# new_9DOF.net
KiCad netlist of a schematic drawn in EAGLE
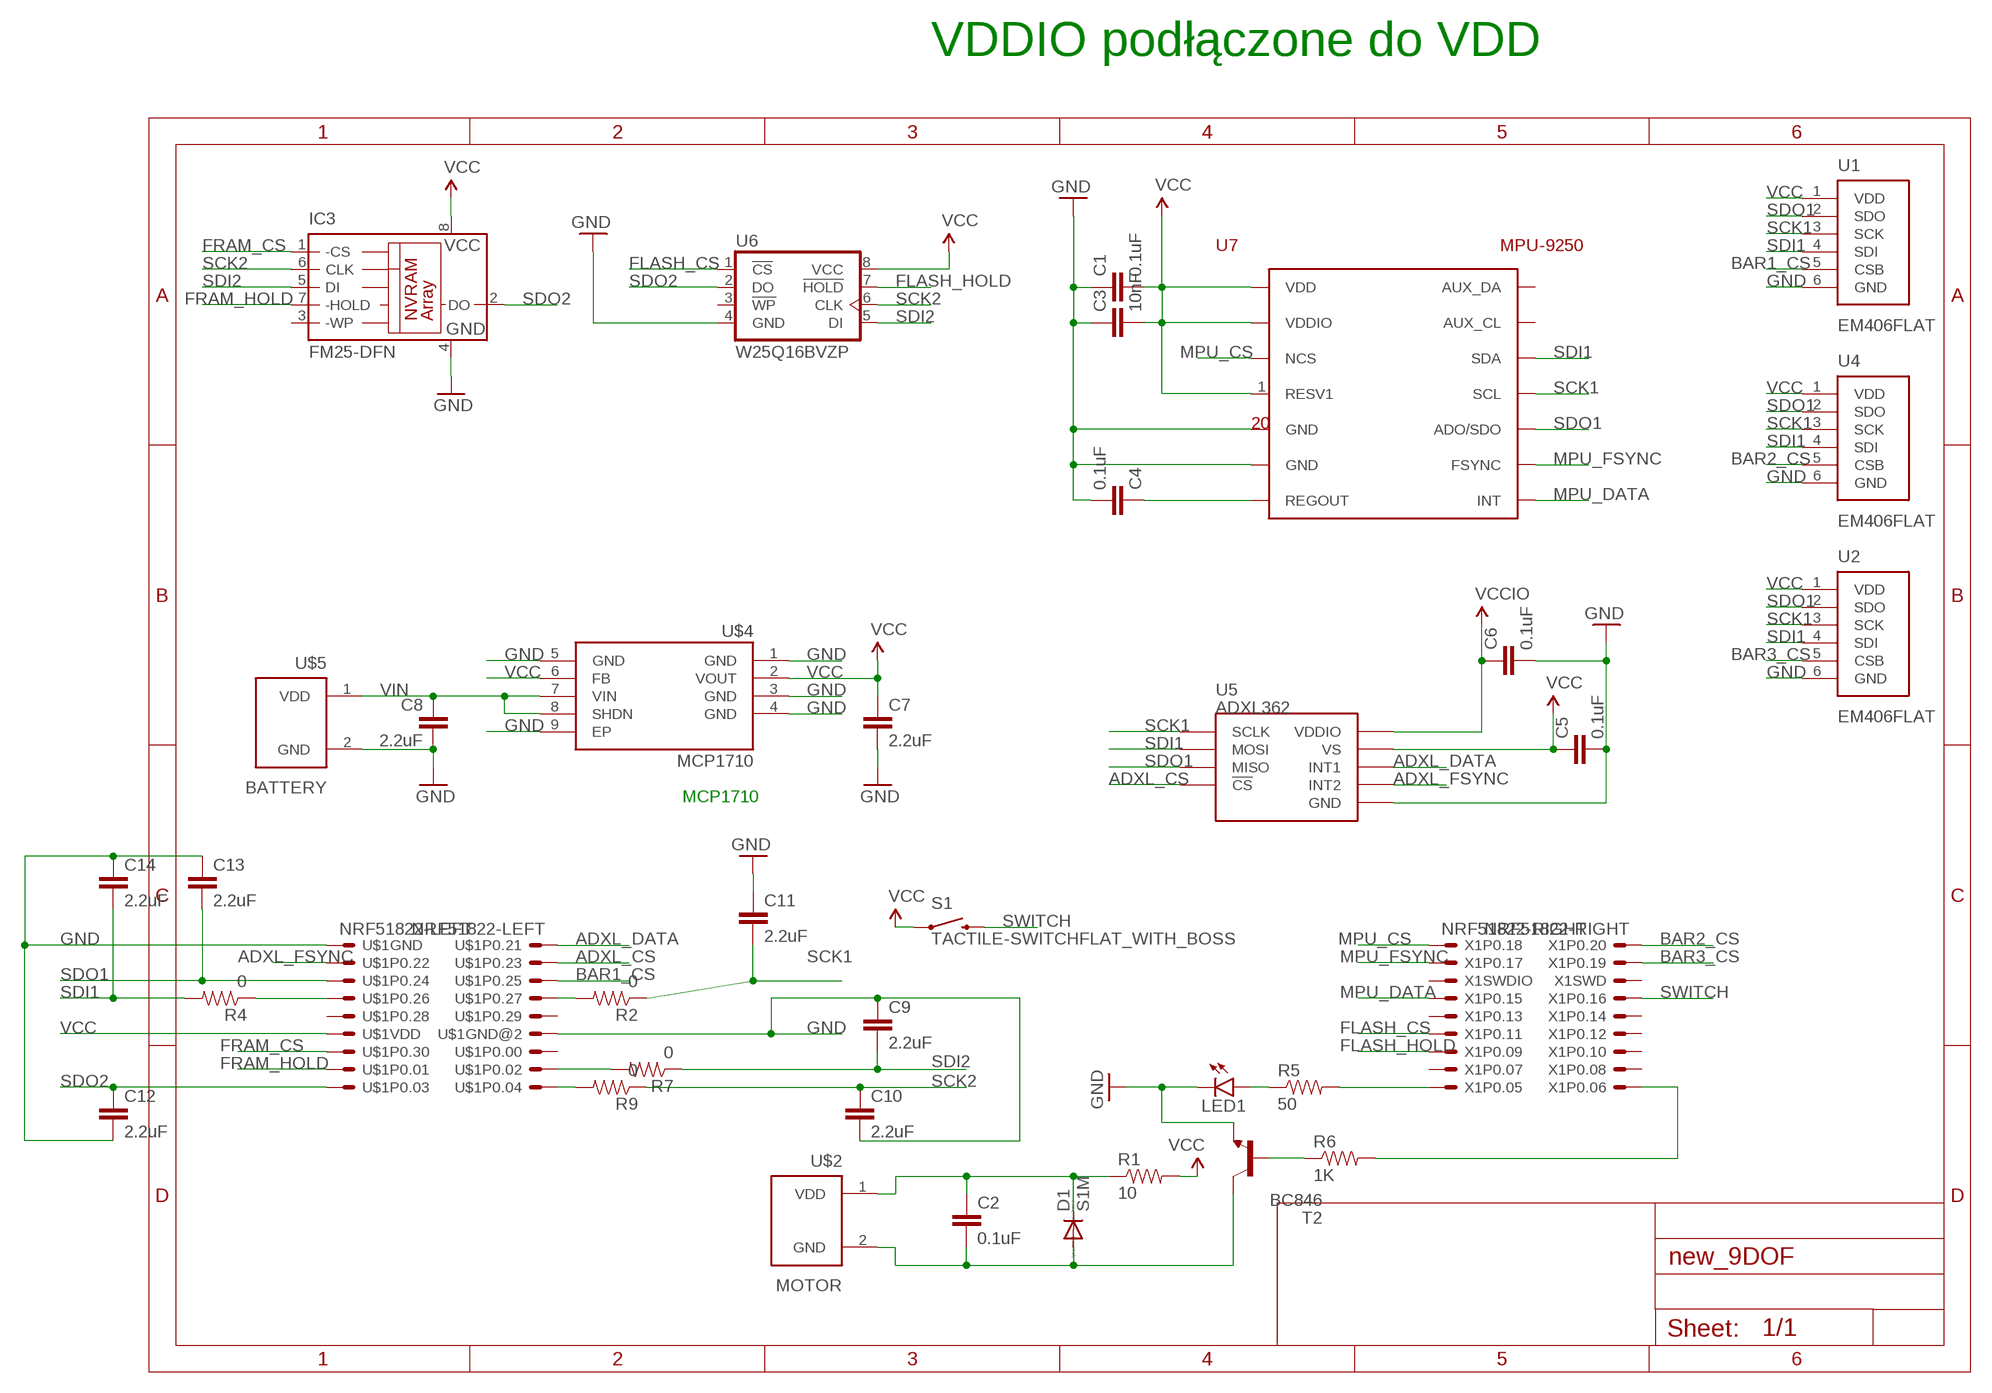
[diagram p0: schematic, sheet 1]

(export (version "E")
  (design (tool "Eeschema 10.0.6"))
  (components
    (comp (ref "C1")
      (value "0.1uF")
      (footprint "eagle-import:0603-CAP")
      (libsource (lib "eagle-import") (part "0.1UF-25V(+80/-20%)(0603)"))
    )
    (comp (ref "C2")
      (value "0.1uF")
      (footprint "eagle-import:0603-CAP")
      (libsource (lib "eagle-import") (part "0.1UF-25V(+80/-20%)(0603)"))
    )
    (comp (ref "C3")
      (value "10nF")
      (footprint "eagle-import:0603-CAP")
      (libsource (lib "eagle-import") (part "0.1UF-25V(+80/-20%)(0603)"))
    )
    (comp (ref "C4")
      (value "0.1uF")
      (footprint "eagle-import:0603-CAP")
      (libsource (lib "eagle-import") (part "0.1UF-25V(+80/-20%)(0603)"))
    )
    (comp (ref "C5")
      (value "0.1uF")
      (footprint "eagle-import:0603-CAP")
      (libsource (lib "eagle-import") (part "0.1UF-25V(+80/-20%)(0603)"))
    )
    (comp (ref "C6")
      (value "0.1uF")
      (footprint "eagle-import:0603-CAP")
      (libsource (lib "eagle-import") (part "0.1UF-25V(+80/-20%)(0603)"))
    )
    (comp (ref "C7")
      (value "2.2uF")
      (footprint "eagle-import:0603-CAP")
      (libsource (lib "eagle-import") (part "0.1UF-25V(+80/-20%)(0603)"))
    )
    (comp (ref "C8")
      (value "2.2uF")
      (footprint "eagle-import:0603-CAP")
      (libsource (lib "eagle-import") (part "0.1UF-25V(+80/-20%)(0603)"))
    )
    (comp (ref "C9")
      (value "2.2uF")
      (footprint "eagle-import:0603-CAP")
      (libsource (lib "eagle-import") (part "0.1UF-25V(+80/-20%)(0603)"))
    )
    (comp (ref "C10")
      (value "2.2uF")
      (footprint "eagle-import:0603-CAP")
      (libsource (lib "eagle-import") (part "0.1UF-25V(+80/-20%)(0603)"))
    )
    (comp (ref "C11")
      (value "2.2uF")
      (footprint "eagle-import:0603-CAP")
      (libsource (lib "eagle-import") (part "0.1UF-25V(+80/-20%)(0603)"))
    )
    (comp (ref "C12")
      (value "2.2uF")
      (footprint "eagle-import:0603-CAP")
      (libsource (lib "eagle-import") (part "0.1UF-25V(+80/-20%)(0603)"))
    )
    (comp (ref "C13")
      (value "2.2uF")
      (footprint "eagle-import:0603-CAP")
      (libsource (lib "eagle-import") (part "0.1UF-25V(+80/-20%)(0603)"))
    )
    (comp (ref "C14")
      (value "2.2uF")
      (footprint "eagle-import:0603-CAP")
      (libsource (lib "eagle-import") (part "0.1UF-25V(+80/-20%)(0603)"))
    )
    (comp (ref "D1")
      (value "S1M")
      (footprint "eagle-import:SMA")
      (libsource (lib "eagle-import") (part "S1M"))
    )
    (comp (ref "IC3")
      (value "FM25-DFN")
      (footprint "eagle-import:DFN-8")
      (libsource (lib "eagle-import") (part "FM25-DFN"))
    )
    (comp (ref "LED1")
      (value "LED0603")
      (footprint "eagle-import:LED-0603")
      (libsource (lib "eagle-import") (part "LED0603"))
    )
    (comp (ref "R1")
      (value "10")
      (footprint "eagle-import:0603-RES")
      (libsource (lib "eagle-import") (part "1KOHM1/10W1%(0603)"))
    )
    (comp (ref "R2")
      (value "0")
      (footprint "eagle-import:0603-RES")
      (libsource (lib "eagle-import") (part "100OHM1/10W1%(0603)"))
    )
    (comp (ref "R4")
      (value "0")
      (footprint "eagle-import:0603-RES")
      (libsource (lib "eagle-import") (part "100OHM1/10W1%(0603)"))
    )
    (comp (ref "R5")
      (value "50")
      (footprint "eagle-import:0603-RES")
      (libsource (lib "eagle-import") (part "100OHM1/10W1%(0603)"))
    )
    (comp (ref "R6")
      (value "1K")
      (footprint "eagle-import:0603-RES")
      (libsource (lib "eagle-import") (part "1KOHM1/10W1%(0603)"))
    )
    (comp (ref "R7")
      (value "0")
      (footprint "eagle-import:0603-RES")
      (libsource (lib "eagle-import") (part "100OHM1/10W1%(0603)"))
    )
    (comp (ref "R9")
      (value "0")
      (footprint "eagle-import:0603-RES")
      (libsource (lib "eagle-import") (part "100OHM1/10W1%(0603)"))
    )
    (comp (ref "S1")
      (value "TACTILE-SWITCHFLAT_WITH_BOSS")
      (footprint "eagle-import:TACTILE-SWITCH-SMD")
      (libsource (lib "eagle-import") (part "TACTILE-SWITCHFLAT_WITH_BOSS"))
    )
    (comp (ref "T2")
      (value "BC846")
      (footprint "eagle-import:SOT23")
      (libsource (lib "eagle-import") (part "BC846"))
    )
    (comp (ref "U$1")
      (value "NRF51822-LEFT")
      (footprint "eagle-import:NRF51822-LEFT")
      (fields (field (name "MPN") "NRF51822-left"))
      (libsource (lib "eagle-import") (part "NRF51822-LEFT"))
    )
    (comp (ref "U$2")
      (value "MOTOR")
      (footprint "eagle-import:EM406-2PIN")
      (libsource (lib "eagle-import") (part "EM406-2PINFLAT"))
    )
    (comp (ref "U$4")
      (value "MCP1710")
      (footprint "eagle-import:MCP1710")
      (libsource (lib "eagle-import") (part "MCP1710"))
    )
    (comp (ref "U$5")
      (value "BATTERY")
      (footprint "eagle-import:EM406-2PIN")
      (libsource (lib "eagle-import") (part "EM406-2PINFLAT"))
    )
    (comp (ref "U1")
      (value "EM406FLAT")
      (footprint "eagle-import:EM406-FLAT")
      (libsource (lib "eagle-import") (part "EM406FLAT"))
    )
    (comp (ref "U2")
      (value "EM406FLAT")
      (footprint "eagle-import:EM406-FLAT")
      (libsource (lib "eagle-import") (part "EM406FLAT"))
    )
    (comp (ref "U4")
      (value "EM406FLAT")
      (footprint "eagle-import:EM406-FLAT")
      (libsource (lib "eagle-import") (part "EM406FLAT"))
    )
    (comp (ref "U5")
      (value "ADXL362")
      (footprint "eagle-import:ADXL362-1_1")
      (libsource (lib "eagle-import") (part "ADXL362ADXL362-1{colon}1"))
    )
    (comp (ref "U6")
      (value "W25Q16BVZP")
      (footprint "eagle-import:WSON8")
      (libsource (lib "eagle-import") (part "W25Q16BVZP"))
    )
    (comp (ref "U7")
      (value "MPU-9250")
      (footprint "eagle-import:MPU-9250")
      (libsource (lib "eagle-import") (part "MPU-9250"))
    )
    (comp (ref "X1")
      (value "NRF51822-RIGHT")
      (footprint "eagle-import:NRF51822-RIGHT")
      (fields (field (name "MPN") "NRF51822-right"))
      (libsource (lib "eagle-import") (part "NRF51822-RIGHT"))
    )
  )
  (nets
    (net (code "1") (name "/ADXL_CS") (class "Default")
      (node (ref "U$1") (pin "4") (pinfunction "S_4") (pintype "passive"))
      (node (ref "U5") (pin "P$8") (pinfunction "~{CS}_P$8") (pintype "bidirectional"))
    )
    (net (code "2") (name "/ADXL_DATA") (class "Default")
      (node (ref "U$1") (pin "2") (pinfunction "S_2") (pintype "passive"))
      (node (ref "U5") (pin "P$11") (pinfunction "INT1_P$11") (pintype "bidirectional"))
    )
    (net (code "3") (name "/ADXL_FSYNC") (class "Default")
      (node (ref "U$1") (pin "3") (pinfunction "S_3") (pintype "passive"))
      (node (ref "U5") (pin "P$9") (pinfunction "INT2_P$9") (pintype "bidirectional"))
    )
    (net (code "4") (name "/BAR1_CS") (class "Default")
      (node (ref "U$1") (pin "6") (pinfunction "S_6") (pintype "passive"))
      (node (ref "U1") (pin "5") (pinfunction "CSB_5") (pintype "bidirectional"))
    )
    (net (code "5") (name "/BAR2_CS") (class "Default")
      (node (ref "U4") (pin "5") (pinfunction "CSB_5") (pintype "bidirectional"))
      (node (ref "X1") (pin "2") (pinfunction "S_2") (pintype "passive"))
    )
    (net (code "6") (name "/BAR3_CS") (class "Default")
      (node (ref "U2") (pin "5") (pinfunction "CSB_5") (pintype "bidirectional"))
      (node (ref "X1") (pin "4") (pinfunction "S_4") (pintype "passive"))
    )
    (net (code "7") (name "/FLASH_CS") (class "Default")
      (node (ref "U6") (pin "1") (pinfunction "~{CS}_1") (pintype "input"))
      (node (ref "X1") (pin "11") (pinfunction "S_11") (pintype "passive"))
    )
    (net (code "8") (name "/FLASH_HOLD") (class "Default")
      (node (ref "U6") (pin "7") (pinfunction "~{HOLD}_7") (pintype "input"))
      (node (ref "X1") (pin "13") (pinfunction "S_13") (pintype "passive"))
    )
    (net (code "9") (name "/FRAM_CS") (class "Default")
      (node (ref "IC3") (pin "1") (pinfunction "-CS_1") (pintype "input"))
      (node (ref "U$1") (pin "13") (pinfunction "S_13") (pintype "passive"))
    )
    (net (code "10") (name "/FRAM_HOLD") (class "Default")
      (node (ref "IC3") (pin "7") (pinfunction "-HOLD_7") (pintype "input"))
      (node (ref "U$1") (pin "15") (pinfunction "S_15") (pintype "passive"))
    )
    (net (code "11") (name "/MPU_CS") (class "Default")
      (node (ref "U7") (pin "22") (pinfunction "NCS_22") (pintype "bidirectional"))
      (node (ref "X1") (pin "1") (pinfunction "S_1") (pintype "passive"))
    )
    (net (code "12") (name "/MPU_DATA") (class "Default")
      (node (ref "U7") (pin "12") (pinfunction "INT_12") (pintype "bidirectional"))
      (node (ref "X1") (pin "7") (pinfunction "S_7") (pintype "passive"))
    )
    (net (code "13") (name "/MPU_FSYNC") (class "Default")
      (node (ref "U7") (pin "11") (pinfunction "FSYNC_11") (pintype "bidirectional"))
      (node (ref "X1") (pin "3") (pinfunction "S_3") (pintype "passive"))
    )
    (net (code "14") (name "/SCK1") (class "Default")
      (node (ref "C11") (pin "2") (pinfunction "2_2") (pintype "passive"))
      (node (ref "R2") (pin "1") (pinfunction "1_1") (pintype "passive"))
      (node (ref "U1") (pin "3") (pinfunction "SCK_3") (pintype "bidirectional"))
      (node (ref "U2") (pin "3") (pinfunction "SCK_3") (pintype "bidirectional"))
      (node (ref "U4") (pin "3") (pinfunction "SCK_3") (pintype "bidirectional"))
      (node (ref "U5") (pin "P$4") (pinfunction "SCLK_P$4") (pintype "bidirectional"))
      (node (ref "U7") (pin "23") (pinfunction "SCL_23") (pintype "bidirectional"))
    )
    (net (code "15") (name "/SCK2") (class "Default")
      (node (ref "C10") (pin "1") (pinfunction "1_1") (pintype "passive"))
      (node (ref "IC3") (pin "6") (pinfunction "CLK_6") (pintype "input"))
      (node (ref "R9") (pin "1") (pinfunction "1_1") (pintype "passive"))
      (node (ref "U6") (pin "6") (pinfunction "CLK_6") (pintype "input"))
    )
    (net (code "16") (name "/SDI1") (class "Default")
      (node (ref "C14") (pin "2") (pinfunction "2_2") (pintype "passive"))
      (node (ref "R4") (pin "2") (pinfunction "2_2") (pintype "passive"))
      (node (ref "U1") (pin "4") (pinfunction "SDI_4") (pintype "bidirectional"))
      (node (ref "U2") (pin "4") (pinfunction "SDI_4") (pintype "bidirectional"))
      (node (ref "U4") (pin "4") (pinfunction "SDI_4") (pintype "bidirectional"))
      (node (ref "U5") (pin "P$6") (pinfunction "MOSI_P$6") (pintype "bidirectional"))
      (node (ref "U7") (pin "24") (pinfunction "SDA_24") (pintype "bidirectional"))
    )
    (net (code "17") (name "/SDI2") (class "Default")
      (node (ref "C9") (pin "2") (pinfunction "2_2") (pintype "passive"))
      (node (ref "IC3") (pin "5") (pinfunction "DI_5") (pintype "input"))
      (node (ref "R7") (pin "1") (pinfunction "1_1") (pintype "passive"))
      (node (ref "U6") (pin "5") (pinfunction "DI_5") (pintype "input"))
    )
    (net (code "18") (name "/SDO1") (class "Default")
      (node (ref "C13") (pin "2") (pinfunction "2_2") (pintype "passive"))
      (node (ref "U$1") (pin "5") (pinfunction "S_5") (pintype "passive"))
      (node (ref "U1") (pin "2") (pinfunction "SDO_2") (pintype "bidirectional"))
      (node (ref "U2") (pin "2") (pinfunction "SDO_2") (pintype "bidirectional"))
      (node (ref "U4") (pin "2") (pinfunction "SDO_2") (pintype "bidirectional"))
      (node (ref "U5") (pin "P$7") (pinfunction "MISO_P$7") (pintype "bidirectional"))
      (node (ref "U7") (pin "9") (pinfunction "ADO/SDO_9") (pintype "bidirectional"))
    )
    (net (code "19") (name "/SDO2") (class "Default")
      (node (ref "C12") (pin "1") (pinfunction "1_1") (pintype "passive"))
      (node (ref "IC3") (pin "2") (pinfunction "DO_2") (pintype "output"))
      (node (ref "U$1") (pin "17") (pinfunction "S_17") (pintype "passive"))
      (node (ref "U6") (pin "2") (pinfunction "DO_2") (pintype "output"))
    )
    (net (code "20") (name "/SWITCH") (class "Default")
      (node (ref "S1") (pin "2") (pinfunction "2_2") (pintype "passive"))
      (node (ref "X1") (pin "8") (pinfunction "S_8") (pintype "passive"))
    )
    (net (code "21") (name "/VIN") (class "Default")
      (node (ref "C8") (pin "1") (pinfunction "1_1") (pintype "passive"))
      (node (ref "U$4") (pin "7") (pinfunction "VIN_7") (pintype "bidirectional"))
      (node (ref "U$4") (pin "8") (pinfunction "SHDN_8") (pintype "bidirectional"))
      (node (ref "U$5") (pin "1") (pinfunction "VDD_1") (pintype "bidirectional"))
    )
    (net (code "22") (name "GND") (class "Default")
      (node (ref "C1") (pin "1") (pinfunction "1_1") (pintype "passive"))
      (node (ref "C10") (pin "2") (pinfunction "2_2") (pintype "passive"))
      (node (ref "C11") (pin "1") (pinfunction "1_1") (pintype "passive"))
      (node (ref "C12") (pin "2") (pinfunction "2_2") (pintype "passive"))
      (node (ref "C13") (pin "1") (pinfunction "1_1") (pintype "passive"))
      (node (ref "C14") (pin "1") (pinfunction "1_1") (pintype "passive"))
      (node (ref "C3") (pin "1") (pinfunction "1_1") (pintype "passive"))
      (node (ref "C4") (pin "2") (pinfunction "2_2") (pintype "passive"))
      (node (ref "C5") (pin "2") (pinfunction "2_2") (pintype "passive"))
      (node (ref "C6") (pin "2") (pinfunction "2_2") (pintype "passive"))
      (node (ref "C7") (pin "2") (pinfunction "2_2") (pintype "passive"))
      (node (ref "C8") (pin "2") (pinfunction "2_2") (pintype "passive"))
      (node (ref "C9") (pin "1") (pinfunction "1_1") (pintype "passive"))
      (node (ref "IC3") (pin "4") (pinfunction "GND_4") (pintype "power_in"))
      (node (ref "LED1") (pin "C") (pinfunction "C_C") (pintype "passive"))
      (node (ref "T2") (pin "2") (pinfunction "E_2") (pintype "passive"))
      (node (ref "U$1") (pin "1") (pinfunction "S_1") (pintype "passive"))
      (node (ref "U$1") (pin "12") (pinfunction "S_12") (pintype "passive"))
      (node (ref "U$4") (pin "1") (pinfunction "GND_1") (pintype "bidirectional"))
      (node (ref "U$4") (pin "3") (pinfunction "GND_3") (pintype "bidirectional"))
      (node (ref "U$4") (pin "4") (pinfunction "GND_4") (pintype "bidirectional"))
      (node (ref "U$4") (pin "5") (pinfunction "GND_5") (pintype "bidirectional"))
      (node (ref "U$4") (pin "9") (pinfunction "EP_9") (pintype "bidirectional"))
      (node (ref "U$5") (pin "2") (pinfunction "GND_2") (pintype "bidirectional"))
      (node (ref "U1") (pin "6") (pinfunction "GND_6") (pintype "bidirectional"))
      (node (ref "U2") (pin "6") (pinfunction "GND_6") (pintype "bidirectional"))
      (node (ref "U4") (pin "6") (pinfunction "GND_6") (pintype "bidirectional"))
      (node (ref "U5") (pin "P$12") (pinfunction "GND_P$12") (pintype "bidirectional"))
      (node (ref "U5") (pin "P$13") (pinfunction "GND_P$13") (pintype "bidirectional"))
      (node (ref "U5") (pin "P$16") (pinfunction "GND_P$16") (pintype "bidirectional"))
      (node (ref "U6") (pin "4") (pinfunction "GND_4") (pintype "power_in"))
      (node (ref "U7") (pin "18") (pinfunction "GND_18") (pintype "power_in"))
      (node (ref "U7") (pin "20") (pinfunction "GND_20") (pintype "power_in"))
    )
    (net (code "23") (name "Net-(LED1-PadA)") (class "Default")
      (node (ref "LED1") (pin "A") (pinfunction "A_A") (pintype "passive"))
      (node (ref "R5") (pin "1") (pinfunction "1_1") (pintype "passive"))
    )
    (net (code "24") (name "Net-(T2-B)") (class "Default")
      (node (ref "R6") (pin "1") (pinfunction "1_1") (pintype "passive"))
      (node (ref "T2") (pin "1") (pinfunction "B_1") (pintype "passive"))
    )
    (net (code "25") (name "Net-(T2-C)") (class "Default")
      (node (ref "C2") (pin "2") (pinfunction "2_2") (pintype "passive"))
      (node (ref "D1") (pin "A") (pinfunction "A_A") (pintype "passive"))
      (node (ref "T2") (pin "3") (pinfunction "C_3") (pintype "passive"))
      (node (ref "U$2") (pin "2") (pinfunction "GND_2") (pintype "bidirectional"))
    )
    (net (code "26") (name "Net-(U$1E-S)") (class "Default")
      (node (ref "R7") (pin "2") (pinfunction "2_2") (pintype "passive"))
      (node (ref "U$1") (pin "16") (pinfunction "S_16") (pintype "passive"))
    )
    (net (code "27") (name "Net-(U$1G-S)") (class "Default")
      (node (ref "R9") (pin "2") (pinfunction "2_2") (pintype "passive"))
      (node (ref "U$1") (pin "18") (pinfunction "S_18") (pintype "passive"))
    )
    (net (code "28") (name "Net-(U$1M-S)") (class "Default")
      (node (ref "R4") (pin "1") (pinfunction "1_1") (pintype "passive"))
      (node (ref "U$1") (pin "7") (pinfunction "S_7") (pintype "passive"))
    )
    (net (code "29") (name "Net-(U$1N-S)") (class "Default")
      (node (ref "R2") (pin "2") (pinfunction "2_2") (pintype "passive"))
      (node (ref "U$1") (pin "8") (pinfunction "S_8") (pintype "passive"))
    )
    (net (code "30") (name "Net-(U$2-VDD)") (class "Default")
      (node (ref "C2") (pin "1") (pinfunction "1_1") (pintype "passive"))
      (node (ref "D1") (pin "C") (pinfunction "C_C") (pintype "passive"))
      (node (ref "R1") (pin "1") (pinfunction "1_1") (pintype "passive"))
      (node (ref "U$2") (pin "1") (pinfunction "VDD_1") (pintype "bidirectional"))
    )
    (net (code "31") (name "Net-(U7-REGOUT)") (class "Default")
      (node (ref "C4") (pin "1") (pinfunction "1_1") (pintype "passive"))
      (node (ref "U7") (pin "10") (pinfunction "REGOUT_10") (pintype "bidirectional"))
    )
    (net (code "32") (name "Net-(X1A-S)") (class "Default")
      (node (ref "R5") (pin "2") (pinfunction "2_2") (pintype "passive"))
      (node (ref "X1") (pin "17") (pinfunction "S_17") (pintype "passive"))
    )
    (net (code "33") (name "Net-(X1B-S)") (class "Default")
      (node (ref "R6") (pin "2") (pinfunction "2_2") (pintype "passive"))
      (node (ref "X1") (pin "18") (pinfunction "S_18") (pintype "passive"))
    )
    (net (code "34") (name "VCC") (class "Default")
      (node (ref "C1") (pin "2") (pinfunction "2_2") (pintype "passive"))
      (node (ref "C3") (pin "2") (pinfunction "2_2") (pintype "passive"))
      (node (ref "C5") (pin "1") (pinfunction "1_1") (pintype "passive"))
      (node (ref "C7") (pin "1") (pinfunction "1_1") (pintype "passive"))
      (node (ref "IC3") (pin "8") (pinfunction "VCC_8") (pintype "power_in"))
      (node (ref "R1") (pin "2") (pinfunction "2_2") (pintype "passive"))
      (node (ref "S1") (pin "1") (pinfunction "1_1") (pintype "passive"))
      (node (ref "U$1") (pin "11") (pinfunction "S_11") (pintype "passive"))
      (node (ref "U$4") (pin "2") (pinfunction "VOUT_2") (pintype "bidirectional"))
      (node (ref "U$4") (pin "6") (pinfunction "FB_6") (pintype "bidirectional"))
      (node (ref "U1") (pin "1") (pinfunction "VDD_1") (pintype "bidirectional"))
      (node (ref "U2") (pin "1") (pinfunction "VDD_1") (pintype "bidirectional"))
      (node (ref "U4") (pin "1") (pinfunction "VDD_1") (pintype "bidirectional"))
      (node (ref "U5") (pin "P$14") (pinfunction "VS_P$14") (pintype "bidirectional"))
      (node (ref "U6") (pin "8") (pinfunction "VCC_8") (pintype "power_in"))
      (node (ref "U7") (pin "1") (pinfunction "RESV1_1") (pintype "power_in"))
      (node (ref "U7") (pin "13") (pinfunction "VDD_13") (pintype "power_in"))
      (node (ref "U7") (pin "8") (pinfunction "VDDIO_8") (pintype "power_in"))
    )
    (net (code "35") (name "VCCIO") (class "Default")
      (node (ref "C6") (pin "1") (pinfunction "1_1") (pintype "passive"))
      (node (ref "U5") (pin "P$1") (pinfunction "VDDIO_P$1") (pintype "bidirectional"))
    )
    (net (code "36") (name "unconnected-(IC3--WP-Pad3)") (class "Default")
      (node (ref "IC3") (pin "3") (pinfunction "-WP_3") (pintype "input"))
    )
    (net (code "37") (name "unconnected-(U$1C-S-Pad14)") (class "Default")
      (node (ref "U$1") (pin "14") (pinfunction "S_14") (pintype "passive"))
    )
    (net (code "38") (name "unconnected-(U$1O-S-Pad9)") (class "Default")
      (node (ref "U$1") (pin "9") (pinfunction "S_9") (pintype "passive"))
    )
    (net (code "39") (name "unconnected-(U$1P-S-Pad10)") (class "Default")
      (node (ref "U$1") (pin "10") (pinfunction "S_10") (pintype "passive"))
    )
    (net (code "40") (name "unconnected-(U6-~{WP}-Pad3)") (class "Default")
      (node (ref "U6") (pin "3") (pinfunction "~{WP}_3") (pintype "input"))
    )
    (net (code "41") (name "unconnected-(U7-AUX_CL-Pad7)") (class "Default")
      (node (ref "U7") (pin "7") (pinfunction "AUX_CL_7") (pintype "bidirectional"))
    )
    (net (code "42") (name "unconnected-(U7-AUX_DA-Pad21)") (class "Default")
      (node (ref "U7") (pin "21") (pinfunction "AUX_DA_21") (pintype "bidirectional"))
    )
    (net (code "43") (name "unconnected-(X1C-S-Pad15)") (class "Default")
      (node (ref "X1") (pin "15") (pinfunction "S_15") (pintype "passive"))
    )
    (net (code "44") (name "unconnected-(X1D-S-Pad16)") (class "Default")
      (node (ref "X1") (pin "16") (pinfunction "S_16") (pintype "passive"))
    )
    (net (code "45") (name "unconnected-(X1F-S-Pad14)") (class "Default")
      (node (ref "X1") (pin "14") (pinfunction "S_14") (pintype "passive"))
    )
    (net (code "46") (name "unconnected-(X1H-S-Pad12)") (class "Default")
      (node (ref "X1") (pin "12") (pinfunction "S_12") (pintype "passive"))
    )
    (net (code "47") (name "unconnected-(X1I-S-Pad9)") (class "Default")
      (node (ref "X1") (pin "9") (pinfunction "S_9") (pintype "passive"))
    )
    (net (code "48") (name "unconnected-(X1J-S-Pad10)") (class "Default")
      (node (ref "X1") (pin "10") (pinfunction "S_10") (pintype "passive"))
    )
    (net (code "49") (name "unconnected-(X1Q-S-Pad6)") (class "Default")
      (node (ref "X1") (pin "6") (pinfunction "S_6") (pintype "passive"))
    )
    (net (code "50") (name "unconnected-(X1R-S-Pad5)") (class "Default")
      (node (ref "X1") (pin "5") (pinfunction "S_5") (pintype "passive"))
    )
  )
)
